# 003-UI.net
KiCad netlist of a schematic drawn in EAGLE
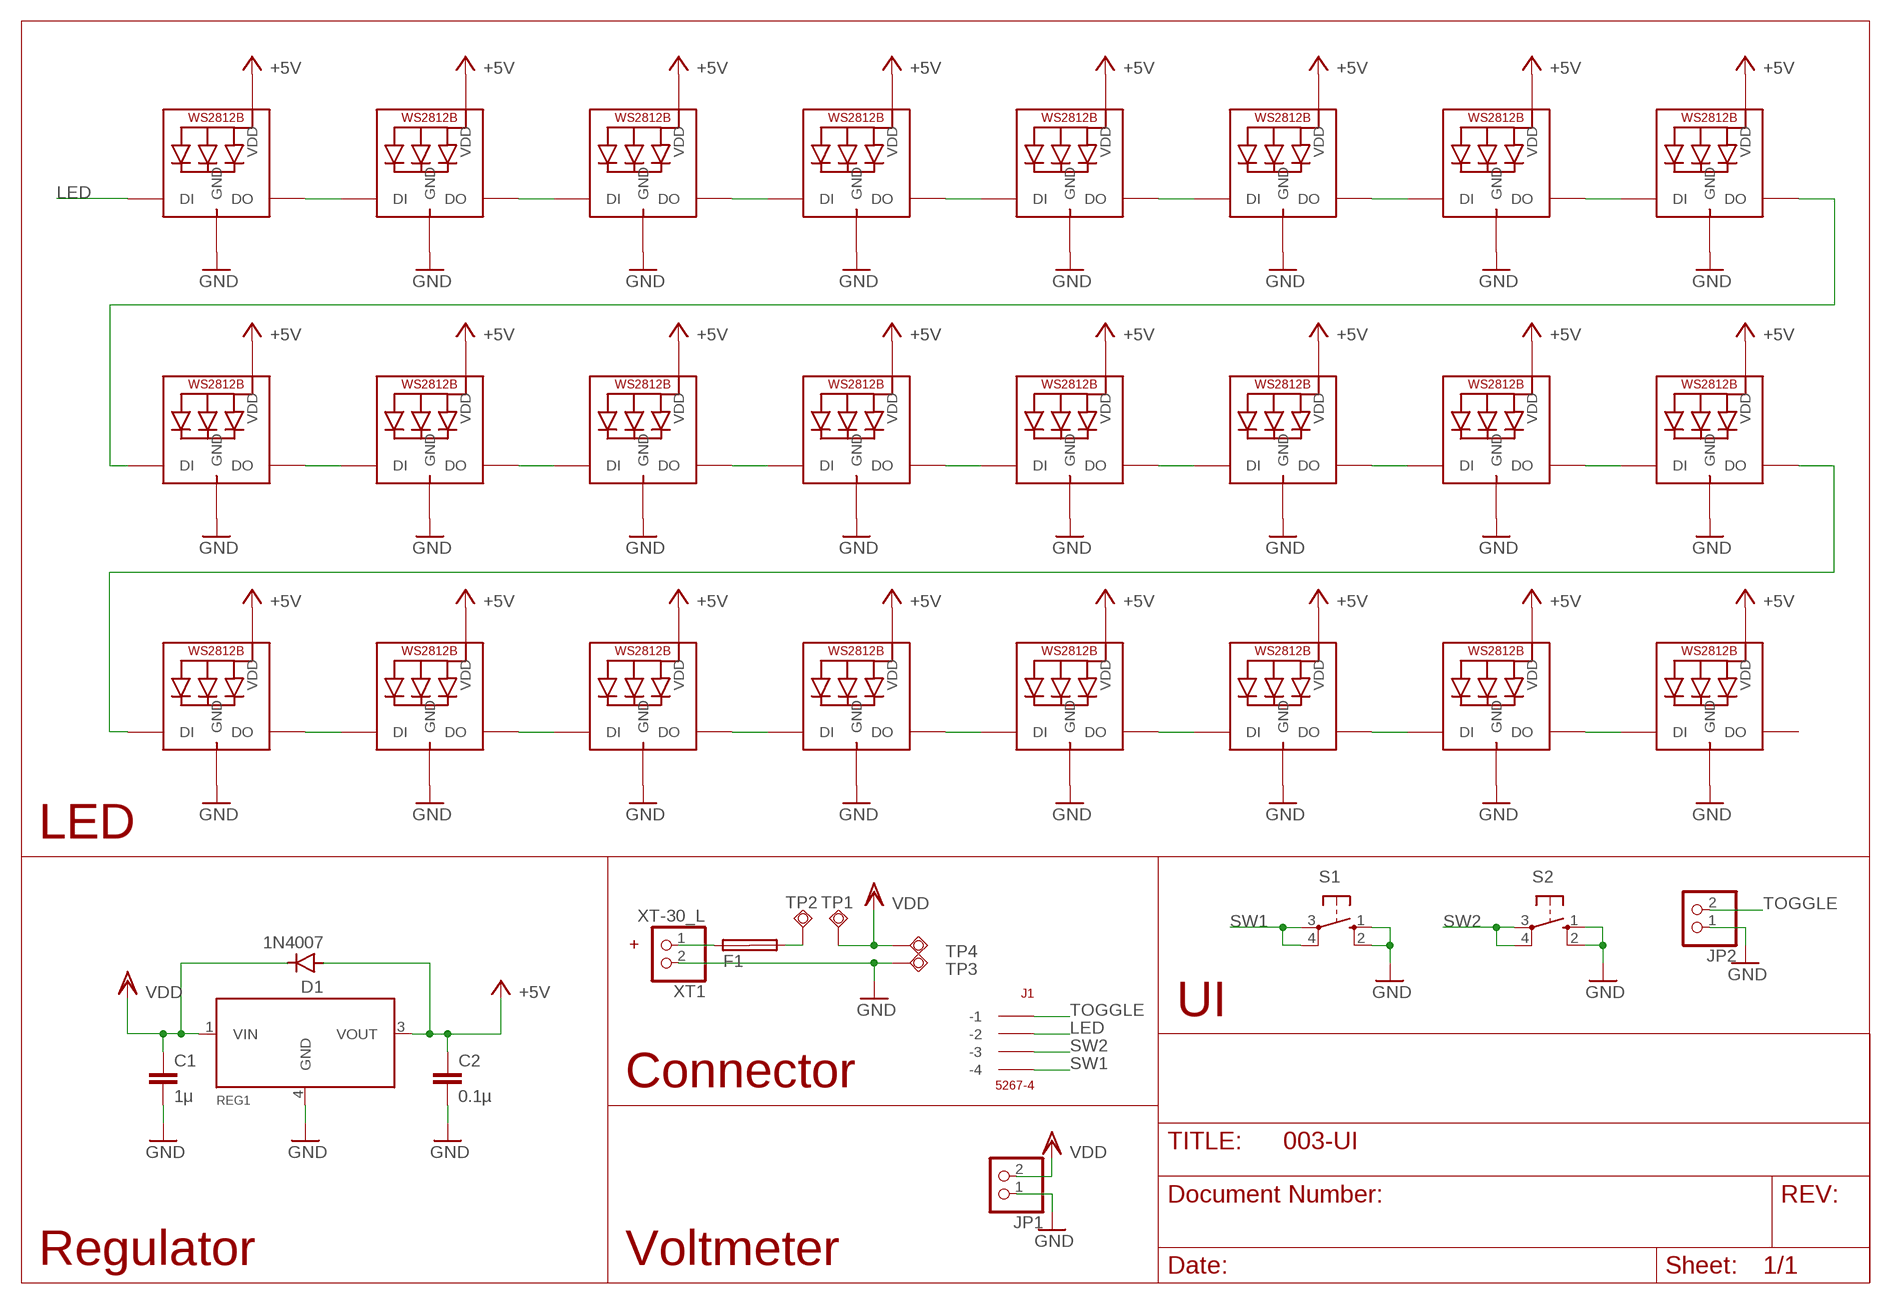
[diagram p0: schematic, sheet 1]

(export (version "E")
  (design (tool "Eeschema 10.0.6"))
  (components
    (comp (ref "C1")
      (value "1μ")
      (footprint "eagle-import:C0402")
      (libsource (lib "eagle-import") (part "C-EUC0402"))
    )
    (comp (ref "C2")
      (value "0.1µ")
      (footprint "eagle-import:C0402")
      (libsource (lib "eagle-import") (part "C-EUC0402"))
    )
    (comp (ref "D1")
      (value "1N4007")
      (footprint "eagle-import:SMA-DO214AC")
      (libsource (lib "eagle-import") (part "GF1"))
    )
    (comp (ref "F1")
      (value "SHK20L")
      (footprint "eagle-import:SHK20L")
      (libsource (lib "eagle-import") (part "SHK20L"))
    )
    (comp (ref "J1")
      (value "5267-4")
      (footprint "eagle-import:5267-4")
      (libsource (lib "eagle-import") (part "5267-4"))
    )
    (comp (ref "JP1")
      (value "PINHD-1X2")
      (footprint "eagle-import:1X02")
      (libsource (lib "eagle-import") (part "PINHD-1X2"))
    )
    (comp (ref "JP2")
      (value "PINHD-1X2")
      (footprint "eagle-import:1X02")
      (libsource (lib "eagle-import") (part "PINHD-1X2"))
    )
    (comp (ref "LED1")
      (value "WS2812B_2020")
      (footprint "eagle-import:WS2812B_2020")
      (libsource (lib "eagle-import") (part "WS2812B_2020"))
    )
    (comp (ref "LED2")
      (value "WS2812B_2020")
      (footprint "eagle-import:WS2812B_2020")
      (libsource (lib "eagle-import") (part "WS2812B_2020"))
    )
    (comp (ref "LED3")
      (value "WS2812B_2020")
      (footprint "eagle-import:WS2812B_2020")
      (libsource (lib "eagle-import") (part "WS2812B_2020"))
    )
    (comp (ref "LED4")
      (value "WS2812B_2020")
      (footprint "eagle-import:WS2812B_2020")
      (libsource (lib "eagle-import") (part "WS2812B_2020"))
    )
    (comp (ref "LED5")
      (value "WS2812B_2020")
      (footprint "eagle-import:WS2812B_2020")
      (libsource (lib "eagle-import") (part "WS2812B_2020"))
    )
    (comp (ref "LED6")
      (value "WS2812B_2020")
      (footprint "eagle-import:WS2812B_2020")
      (libsource (lib "eagle-import") (part "WS2812B_2020"))
    )
    (comp (ref "LED7")
      (value "WS2812B_2020")
      (footprint "eagle-import:WS2812B_2020")
      (libsource (lib "eagle-import") (part "WS2812B_2020"))
    )
    (comp (ref "LED8")
      (value "WS2812B_2020")
      (footprint "eagle-import:WS2812B_2020")
      (libsource (lib "eagle-import") (part "WS2812B_2020"))
    )
    (comp (ref "LED9")
      (value "WS2812B_2020")
      (footprint "eagle-import:WS2812B_2020")
      (libsource (lib "eagle-import") (part "WS2812B_2020"))
    )
    (comp (ref "LED10")
      (value "WS2812B_2020")
      (footprint "eagle-import:WS2812B_2020")
      (libsource (lib "eagle-import") (part "WS2812B_2020"))
    )
    (comp (ref "LED11")
      (value "WS2812B_2020")
      (footprint "eagle-import:WS2812B_2020")
      (libsource (lib "eagle-import") (part "WS2812B_2020"))
    )
    (comp (ref "LED12")
      (value "WS2812B_2020")
      (footprint "eagle-import:WS2812B_2020")
      (libsource (lib "eagle-import") (part "WS2812B_2020"))
    )
    (comp (ref "LED13")
      (value "WS2812B_2020")
      (footprint "eagle-import:WS2812B_2020")
      (libsource (lib "eagle-import") (part "WS2812B_2020"))
    )
    (comp (ref "LED14")
      (value "WS2812B_2020")
      (footprint "eagle-import:WS2812B_2020")
      (libsource (lib "eagle-import") (part "WS2812B_2020"))
    )
    (comp (ref "LED15")
      (value "WS2812B_2020")
      (footprint "eagle-import:WS2812B_2020")
      (libsource (lib "eagle-import") (part "WS2812B_2020"))
    )
    (comp (ref "LED16")
      (value "WS2812B_2020")
      (footprint "eagle-import:WS2812B_2020")
      (libsource (lib "eagle-import") (part "WS2812B_2020"))
    )
    (comp (ref "LED17")
      (value "WS2812B_2020")
      (footprint "eagle-import:WS2812B_2020")
      (libsource (lib "eagle-import") (part "WS2812B_2020"))
    )
    (comp (ref "LED18")
      (value "WS2812B_2020")
      (footprint "eagle-import:WS2812B_2020")
      (libsource (lib "eagle-import") (part "WS2812B_2020"))
    )
    (comp (ref "LED19")
      (value "WS2812B_2020")
      (footprint "eagle-import:WS2812B_2020")
      (libsource (lib "eagle-import") (part "WS2812B_2020"))
    )
    (comp (ref "LED20")
      (value "WS2812B_2020")
      (footprint "eagle-import:WS2812B_2020")
      (libsource (lib "eagle-import") (part "WS2812B_2020"))
    )
    (comp (ref "LED21")
      (value "WS2812B_2020")
      (footprint "eagle-import:WS2812B_2020")
      (libsource (lib "eagle-import") (part "WS2812B_2020"))
    )
    (comp (ref "LED22")
      (value "WS2812B_2020")
      (footprint "eagle-import:WS2812B_2020")
      (libsource (lib "eagle-import") (part "WS2812B_2020"))
    )
    (comp (ref "LED23")
      (value "WS2812B_2020")
      (footprint "eagle-import:WS2812B_2020")
      (libsource (lib "eagle-import") (part "WS2812B_2020"))
    )
    (comp (ref "LED24")
      (value "WS2812B_2020")
      (footprint "eagle-import:WS2812B_2020")
      (libsource (lib "eagle-import") (part "WS2812B_2020"))
    )
    (comp (ref "REG1")
      (value "MYPARTS_NJM7800S-REGULATOR")
      (footprint "eagle-import:MYPARTS_D-PAK_TO252AA")
      (libsource (lib "eagle-import") (part "MYPARTS_NJM7800S-REGULATOR"))
    )
    (comp (ref "S1")
      (value "10-XX")
      (footprint "eagle-import:B3F-10XX")
      (fields (field (name "MPN") "B3F-1000"))
      (libsource (lib "eagle-import") (part "10-XX"))
    )
    (comp (ref "S2")
      (value "10-XX")
      (footprint "eagle-import:B3F-10XX")
      (fields (field (name "MPN") "B3F-1000"))
      (libsource (lib "eagle-import") (part "10-XX"))
    )
    (comp (ref "TP1")
      (value "TPSQPAD1-20")
      (footprint "eagle-import:P1-20")
      (libsource (lib "eagle-import") (part "TPSQPAD1-20"))
    )
    (comp (ref "TP2")
      (value "TPSQPAD1-20")
      (footprint "eagle-import:P1-20")
      (libsource (lib "eagle-import") (part "TPSQPAD1-20"))
    )
    (comp (ref "TP3")
      (value "TPSQPAD1-20")
      (footprint "eagle-import:P1-20")
      (libsource (lib "eagle-import") (part "TPSQPAD1-20"))
    )
    (comp (ref "TP4")
      (value "TPSQPAD1-20")
      (footprint "eagle-import:P1-20")
      (libsource (lib "eagle-import") (part "TPSQPAD1-20"))
    )
    (comp (ref "XT1")
      (value "XT-30_L")
      (footprint "eagle-import:XT-30_L")
      (libsource (lib "eagle-import") (part "XT-30_L"))
    )
  )
  (nets
    (net (code "1") (name "+5V") (class "Default")
      (node (ref "C2") (pin "1") (pinfunction "1_1") (pintype "passive"))
      (node (ref "D1") (pin "A") (pinfunction "A_A") (pintype "passive"))
      (node (ref "LED1") (pin "4") (pinfunction "VDD_4") (pintype "power_in"))
      (node (ref "LED10") (pin "4") (pinfunction "VDD_4") (pintype "power_in"))
      (node (ref "LED11") (pin "4") (pinfunction "VDD_4") (pintype "power_in"))
      (node (ref "LED12") (pin "4") (pinfunction "VDD_4") (pintype "power_in"))
      (node (ref "LED13") (pin "4") (pinfunction "VDD_4") (pintype "power_in"))
      (node (ref "LED14") (pin "4") (pinfunction "VDD_4") (pintype "power_in"))
      (node (ref "LED15") (pin "4") (pinfunction "VDD_4") (pintype "power_in"))
      (node (ref "LED16") (pin "4") (pinfunction "VDD_4") (pintype "power_in"))
      (node (ref "LED17") (pin "4") (pinfunction "VDD_4") (pintype "power_in"))
      (node (ref "LED18") (pin "4") (pinfunction "VDD_4") (pintype "power_in"))
      (node (ref "LED19") (pin "4") (pinfunction "VDD_4") (pintype "power_in"))
      (node (ref "LED2") (pin "4") (pinfunction "VDD_4") (pintype "power_in"))
      (node (ref "LED20") (pin "4") (pinfunction "VDD_4") (pintype "power_in"))
      (node (ref "LED21") (pin "4") (pinfunction "VDD_4") (pintype "power_in"))
      (node (ref "LED22") (pin "4") (pinfunction "VDD_4") (pintype "power_in"))
      (node (ref "LED23") (pin "4") (pinfunction "VDD_4") (pintype "power_in"))
      (node (ref "LED24") (pin "4") (pinfunction "VDD_4") (pintype "power_in"))
      (node (ref "LED3") (pin "4") (pinfunction "VDD_4") (pintype "power_in"))
      (node (ref "LED4") (pin "4") (pinfunction "VDD_4") (pintype "power_in"))
      (node (ref "LED5") (pin "4") (pinfunction "VDD_4") (pintype "power_in"))
      (node (ref "LED6") (pin "4") (pinfunction "VDD_4") (pintype "power_in"))
      (node (ref "LED7") (pin "4") (pinfunction "VDD_4") (pintype "power_in"))
      (node (ref "LED8") (pin "4") (pinfunction "VDD_4") (pintype "power_in"))
      (node (ref "LED9") (pin "4") (pinfunction "VDD_4") (pintype "power_in"))
      (node (ref "REG1") (pin "3") (pinfunction "VOUT_3") (pintype "passive"))
    )
    (net (code "2") (name "/LED") (class "Default")
      (node (ref "J1") (pin "P$2") (pinfunction "-2_P$2") (pintype "bidirectional"))
      (node (ref "LED1") (pin "3") (pinfunction "DI_3") (pintype "input"))
    )
    (net (code "3") (name "/SW1") (class "Default")
      (node (ref "J1") (pin "P$4") (pinfunction "-4_P$4") (pintype "bidirectional"))
      (node (ref "S1") (pin "3") (pinfunction "P_3") (pintype "passive"))
      (node (ref "S1") (pin "4") (pinfunction "P1_4") (pintype "passive"))
    )
    (net (code "4") (name "/SW2") (class "Default")
      (node (ref "J1") (pin "P$3") (pinfunction "-3_P$3") (pintype "bidirectional"))
      (node (ref "S2") (pin "3") (pinfunction "P_3") (pintype "passive"))
      (node (ref "S2") (pin "4") (pinfunction "P1_4") (pintype "passive"))
    )
    (net (code "5") (name "/TOGGLE") (class "Default")
      (node (ref "J1") (pin "P$1") (pinfunction "-1_P$1") (pintype "bidirectional"))
      (node (ref "JP2") (pin "2") (pinfunction "2_2") (pintype "passive"))
    )
    (net (code "6") (name "GND") (class "Default")
      (node (ref "C1") (pin "2") (pinfunction "2_2") (pintype "passive"))
      (node (ref "C2") (pin "2") (pinfunction "2_2") (pintype "passive"))
      (node (ref "JP1") (pin "1") (pinfunction "1_1") (pintype "passive"))
      (node (ref "JP2") (pin "1") (pinfunction "1_1") (pintype "passive"))
      (node (ref "LED1") (pin "2") (pinfunction "GND_2") (pintype "power_in"))
      (node (ref "LED10") (pin "2") (pinfunction "GND_2") (pintype "power_in"))
      (node (ref "LED11") (pin "2") (pinfunction "GND_2") (pintype "power_in"))
      (node (ref "LED12") (pin "2") (pinfunction "GND_2") (pintype "power_in"))
      (node (ref "LED13") (pin "2") (pinfunction "GND_2") (pintype "power_in"))
      (node (ref "LED14") (pin "2") (pinfunction "GND_2") (pintype "power_in"))
      (node (ref "LED15") (pin "2") (pinfunction "GND_2") (pintype "power_in"))
      (node (ref "LED16") (pin "2") (pinfunction "GND_2") (pintype "power_in"))
      (node (ref "LED17") (pin "2") (pinfunction "GND_2") (pintype "power_in"))
      (node (ref "LED18") (pin "2") (pinfunction "GND_2") (pintype "power_in"))
      (node (ref "LED19") (pin "2") (pinfunction "GND_2") (pintype "power_in"))
      (node (ref "LED2") (pin "2") (pinfunction "GND_2") (pintype "power_in"))
      (node (ref "LED20") (pin "2") (pinfunction "GND_2") (pintype "power_in"))
      (node (ref "LED21") (pin "2") (pinfunction "GND_2") (pintype "power_in"))
      (node (ref "LED22") (pin "2") (pinfunction "GND_2") (pintype "power_in"))
      (node (ref "LED23") (pin "2") (pinfunction "GND_2") (pintype "power_in"))
      (node (ref "LED24") (pin "2") (pinfunction "GND_2") (pintype "power_in"))
      (node (ref "LED3") (pin "2") (pinfunction "GND_2") (pintype "power_in"))
      (node (ref "LED4") (pin "2") (pinfunction "GND_2") (pintype "power_in"))
      (node (ref "LED5") (pin "2") (pinfunction "GND_2") (pintype "power_in"))
      (node (ref "LED6") (pin "2") (pinfunction "GND_2") (pintype "power_in"))
      (node (ref "LED7") (pin "2") (pinfunction "GND_2") (pintype "power_in"))
      (node (ref "LED8") (pin "2") (pinfunction "GND_2") (pintype "power_in"))
      (node (ref "LED9") (pin "2") (pinfunction "GND_2") (pintype "power_in"))
      (node (ref "REG1") (pin "4") (pinfunction "GND_4") (pintype "passive"))
      (node (ref "S1") (pin "1") (pinfunction "S_1") (pintype "passive"))
      (node (ref "S1") (pin "2") (pinfunction "S1_2") (pintype "passive"))
      (node (ref "S2") (pin "1") (pinfunction "S_1") (pintype "passive"))
      (node (ref "S2") (pin "2") (pinfunction "S1_2") (pintype "passive"))
      (node (ref "TP3") (pin "TP") (pinfunction "TP_TP") (pintype "input"))
      (node (ref "XT1") (pin "2") (pinfunction "2_2") (pintype "passive"))
    )
    (net (code "7") (name "Net-(F1-Pad1A)") (class "Default")
      (node (ref "F1") (pin "1A") (pinfunction "1A_1A") (pintype "passive"))
      (node (ref "XT1") (pin "1") (pinfunction "1_1") (pintype "passive"))
    )
    (net (code "8") (name "Net-(F1-Pad2A)") (class "Default")
      (node (ref "F1") (pin "2A") (pinfunction "2A_2A") (pintype "passive"))
      (node (ref "TP2") (pin "TP") (pinfunction "TP_TP") (pintype "input"))
    )
    (net (code "9") (name "Net-(LED1-DO)") (class "Default")
      (node (ref "LED1") (pin "1") (pinfunction "DO_1") (pintype "output"))
      (node (ref "LED2") (pin "3") (pinfunction "DI_3") (pintype "input"))
    )
    (net (code "10") (name "Net-(LED2-DO)") (class "Default")
      (node (ref "LED2") (pin "1") (pinfunction "DO_1") (pintype "output"))
      (node (ref "LED3") (pin "3") (pinfunction "DI_3") (pintype "input"))
    )
    (net (code "11") (name "Net-(LED3-DO)") (class "Default")
      (node (ref "LED3") (pin "1") (pinfunction "DO_1") (pintype "output"))
      (node (ref "LED4") (pin "3") (pinfunction "DI_3") (pintype "input"))
    )
    (net (code "12") (name "Net-(LED4-DO)") (class "Default")
      (node (ref "LED4") (pin "1") (pinfunction "DO_1") (pintype "output"))
      (node (ref "LED5") (pin "3") (pinfunction "DI_3") (pintype "input"))
    )
    (net (code "13") (name "Net-(LED5-DO)") (class "Default")
      (node (ref "LED5") (pin "1") (pinfunction "DO_1") (pintype "output"))
      (node (ref "LED6") (pin "3") (pinfunction "DI_3") (pintype "input"))
    )
    (net (code "14") (name "Net-(LED6-DO)") (class "Default")
      (node (ref "LED6") (pin "1") (pinfunction "DO_1") (pintype "output"))
      (node (ref "LED7") (pin "3") (pinfunction "DI_3") (pintype "input"))
    )
    (net (code "15") (name "Net-(LED7-DO)") (class "Default")
      (node (ref "LED7") (pin "1") (pinfunction "DO_1") (pintype "output"))
      (node (ref "LED8") (pin "3") (pinfunction "DI_3") (pintype "input"))
    )
    (net (code "16") (name "Net-(LED8-DO)") (class "Default")
      (node (ref "LED8") (pin "1") (pinfunction "DO_1") (pintype "output"))
      (node (ref "LED9") (pin "3") (pinfunction "DI_3") (pintype "input"))
    )
    (net (code "17") (name "Net-(LED10-DI)") (class "Default")
      (node (ref "LED10") (pin "3") (pinfunction "DI_3") (pintype "input"))
      (node (ref "LED9") (pin "1") (pinfunction "DO_1") (pintype "output"))
    )
    (net (code "18") (name "Net-(LED10-DO)") (class "Default")
      (node (ref "LED10") (pin "1") (pinfunction "DO_1") (pintype "output"))
      (node (ref "LED11") (pin "3") (pinfunction "DI_3") (pintype "input"))
    )
    (net (code "19") (name "Net-(LED11-DO)") (class "Default")
      (node (ref "LED11") (pin "1") (pinfunction "DO_1") (pintype "output"))
      (node (ref "LED12") (pin "3") (pinfunction "DI_3") (pintype "input"))
    )
    (net (code "20") (name "Net-(LED12-DO)") (class "Default")
      (node (ref "LED12") (pin "1") (pinfunction "DO_1") (pintype "output"))
      (node (ref "LED13") (pin "3") (pinfunction "DI_3") (pintype "input"))
    )
    (net (code "21") (name "Net-(LED13-DO)") (class "Default")
      (node (ref "LED13") (pin "1") (pinfunction "DO_1") (pintype "output"))
      (node (ref "LED14") (pin "3") (pinfunction "DI_3") (pintype "input"))
    )
    (net (code "22") (name "Net-(LED14-DO)") (class "Default")
      (node (ref "LED14") (pin "1") (pinfunction "DO_1") (pintype "output"))
      (node (ref "LED15") (pin "3") (pinfunction "DI_3") (pintype "input"))
    )
    (net (code "23") (name "Net-(LED15-DO)") (class "Default")
      (node (ref "LED15") (pin "1") (pinfunction "DO_1") (pintype "output"))
      (node (ref "LED16") (pin "3") (pinfunction "DI_3") (pintype "input"))
    )
    (net (code "24") (name "Net-(LED16-DO)") (class "Default")
      (node (ref "LED16") (pin "1") (pinfunction "DO_1") (pintype "output"))
      (node (ref "LED17") (pin "3") (pinfunction "DI_3") (pintype "input"))
    )
    (net (code "25") (name "Net-(LED17-DO)") (class "Default")
      (node (ref "LED17") (pin "1") (pinfunction "DO_1") (pintype "output"))
      (node (ref "LED18") (pin "3") (pinfunction "DI_3") (pintype "input"))
    )
    (net (code "26") (name "Net-(LED18-DO)") (class "Default")
      (node (ref "LED18") (pin "1") (pinfunction "DO_1") (pintype "output"))
      (node (ref "LED19") (pin "3") (pinfunction "DI_3") (pintype "input"))
    )
    (net (code "27") (name "Net-(LED19-DO)") (class "Default")
      (node (ref "LED19") (pin "1") (pinfunction "DO_1") (pintype "output"))
      (node (ref "LED20") (pin "3") (pinfunction "DI_3") (pintype "input"))
    )
    (net (code "28") (name "Net-(LED20-DO)") (class "Default")
      (node (ref "LED20") (pin "1") (pinfunction "DO_1") (pintype "output"))
      (node (ref "LED21") (pin "3") (pinfunction "DI_3") (pintype "input"))
    )
    (net (code "29") (name "Net-(LED21-DO)") (class "Default")
      (node (ref "LED21") (pin "1") (pinfunction "DO_1") (pintype "output"))
      (node (ref "LED22") (pin "3") (pinfunction "DI_3") (pintype "input"))
    )
    (net (code "30") (name "Net-(LED22-DO)") (class "Default")
      (node (ref "LED22") (pin "1") (pinfunction "DO_1") (pintype "output"))
      (node (ref "LED23") (pin "3") (pinfunction "DI_3") (pintype "input"))
    )
    (net (code "31") (name "Net-(LED23-DO)") (class "Default")
      (node (ref "LED23") (pin "1") (pinfunction "DO_1") (pintype "output"))
      (node (ref "LED24") (pin "3") (pinfunction "DI_3") (pintype "input"))
    )
    (net (code "32") (name "VDD") (class "Default")
      (node (ref "C1") (pin "1") (pinfunction "1_1") (pintype "passive"))
      (node (ref "D1") (pin "K") (pinfunction "C_K") (pintype "passive"))
      (node (ref "JP1") (pin "2") (pinfunction "2_2") (pintype "passive"))
      (node (ref "REG1") (pin "1") (pinfunction "VIN_1") (pintype "passive"))
      (node (ref "TP1") (pin "TP") (pinfunction "TP_TP") (pintype "input"))
      (node (ref "TP4") (pin "TP") (pinfunction "TP_TP") (pintype "input"))
    )
    (net (code "33") (name "unconnected-(F1-Pad1B)") (class "Default")
      (node (ref "F1") (pin "1B") (pinfunction "1B_1B") (pintype "passive"))
    )
    (net (code "34") (name "unconnected-(F1-Pad2B)") (class "Default")
      (node (ref "F1") (pin "2B") (pinfunction "2B_2B") (pintype "passive"))
    )
    (net (code "35") (name "unconnected-(LED24-DO-Pad1)") (class "Default")
      (node (ref "LED24") (pin "1") (pinfunction "DO_1") (pintype "output"))
    )
  )
)
